# buses.net
KiCad netlist of a schematic drawn in EAGLE
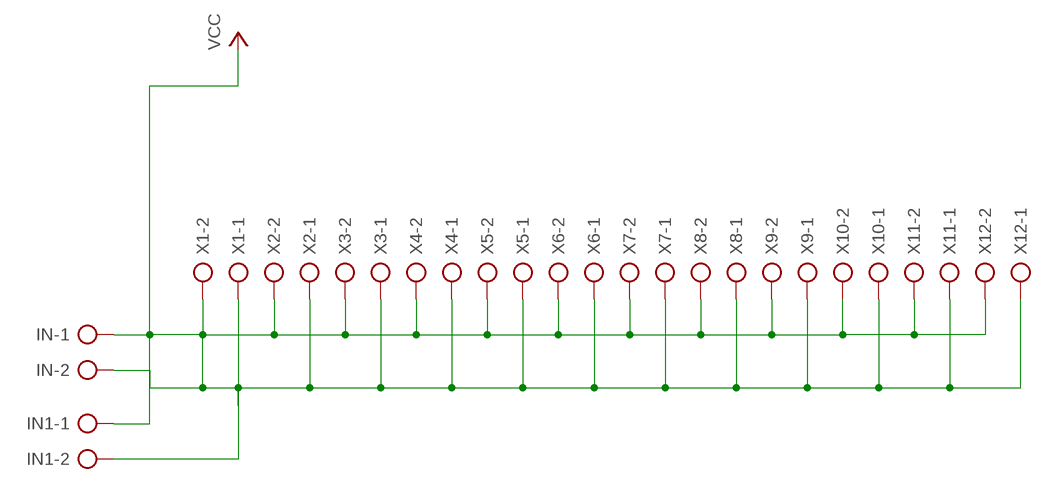
[diagram p0: schematic, sheet 1]

(export (version "E")
  (design (tool "Eeschema 10.0.6"))
  (components
    (comp (ref "IN")
      (value "AK500/2-H")
      (footprint "eagle-import:AK500_2-H")
      (libsource (lib "eagle-import") (part "AK500/2-H"))
    )
    (comp (ref "IN1")
      (value "AK500/2-H")
      (footprint "eagle-import:AK500_2-H")
      (libsource (lib "eagle-import") (part "AK500/2-H"))
    )
    (comp (ref "X1")
      (value "AK500/2-H")
      (footprint "eagle-import:AK500_2-H")
      (libsource (lib "eagle-import") (part "AK500/2-H"))
    )
    (comp (ref "X2")
      (value "AK500/2-H")
      (footprint "eagle-import:AK500_2-H")
      (libsource (lib "eagle-import") (part "AK500/2-H"))
    )
    (comp (ref "X3")
      (value "AK500/2-H")
      (footprint "eagle-import:AK500_2-H")
      (libsource (lib "eagle-import") (part "AK500/2-H"))
    )
    (comp (ref "X4")
      (value "AK500/2-H")
      (footprint "eagle-import:AK500_2-H")
      (libsource (lib "eagle-import") (part "AK500/2-H"))
    )
    (comp (ref "X5")
      (value "AK500/2-H")
      (footprint "eagle-import:AK500_2-H")
      (libsource (lib "eagle-import") (part "AK500/2-H"))
    )
    (comp (ref "X6")
      (value "AK500/2-H")
      (footprint "eagle-import:AK500_2-H")
      (libsource (lib "eagle-import") (part "AK500/2-H"))
    )
    (comp (ref "X7")
      (value "AK500/2-H")
      (footprint "eagle-import:AK500_2-H")
      (libsource (lib "eagle-import") (part "AK500/2-H"))
    )
    (comp (ref "X8")
      (value "AK500/2-H")
      (footprint "eagle-import:AK500_2-H")
      (libsource (lib "eagle-import") (part "AK500/2-H"))
    )
    (comp (ref "X9")
      (value "AK500/2-H")
      (footprint "eagle-import:AK500_2-H")
      (libsource (lib "eagle-import") (part "AK500/2-H"))
    )
    (comp (ref "X10")
      (value "AK500/2-H")
      (footprint "eagle-import:AK500_2-H")
      (libsource (lib "eagle-import") (part "AK500/2-H"))
    )
    (comp (ref "X11")
      (value "AK500/2-H")
      (footprint "eagle-import:AK500_2-H")
      (libsource (lib "eagle-import") (part "AK500/2-H"))
    )
    (comp (ref "X12")
      (value "AK500/2-H")
      (footprint "eagle-import:AK500_2-H")
      (libsource (lib "eagle-import") (part "AK500/2-H"))
    )
  )
  (nets
    (net (code "1") (name "VCC") (class "Default")
      (node (ref "IN") (pin "1") (pinfunction "KL_1") (pintype "passive"))
      (node (ref "IN") (pin "2") (pinfunction "KL_2") (pintype "passive"))
      (node (ref "IN1") (pin "1") (pinfunction "KL_1") (pintype "passive"))
      (node (ref "IN1") (pin "2") (pinfunction "KL_2") (pintype "passive"))
      (node (ref "X1") (pin "1") (pinfunction "KL_1") (pintype "passive"))
      (node (ref "X1") (pin "2") (pinfunction "KL_2") (pintype "passive"))
      (node (ref "X10") (pin "1") (pinfunction "KL_1") (pintype "passive"))
      (node (ref "X10") (pin "2") (pinfunction "KL_2") (pintype "passive"))
      (node (ref "X11") (pin "1") (pinfunction "KL_1") (pintype "passive"))
      (node (ref "X11") (pin "2") (pinfunction "KL_2") (pintype "passive"))
      (node (ref "X12") (pin "1") (pinfunction "KL_1") (pintype "passive"))
      (node (ref "X12") (pin "2") (pinfunction "KL_2") (pintype "passive"))
      (node (ref "X2") (pin "1") (pinfunction "KL_1") (pintype "passive"))
      (node (ref "X2") (pin "2") (pinfunction "KL_2") (pintype "passive"))
      (node (ref "X3") (pin "1") (pinfunction "KL_1") (pintype "passive"))
      (node (ref "X3") (pin "2") (pinfunction "KL_2") (pintype "passive"))
      (node (ref "X4") (pin "1") (pinfunction "KL_1") (pintype "passive"))
      (node (ref "X4") (pin "2") (pinfunction "KL_2") (pintype "passive"))
      (node (ref "X5") (pin "1") (pinfunction "KL_1") (pintype "passive"))
      (node (ref "X5") (pin "2") (pinfunction "KL_2") (pintype "passive"))
      (node (ref "X6") (pin "1") (pinfunction "KL_1") (pintype "passive"))
      (node (ref "X6") (pin "2") (pinfunction "KL_2") (pintype "passive"))
      (node (ref "X7") (pin "1") (pinfunction "KL_1") (pintype "passive"))
      (node (ref "X7") (pin "2") (pinfunction "KL_2") (pintype "passive"))
      (node (ref "X8") (pin "1") (pinfunction "KL_1") (pintype "passive"))
      (node (ref "X8") (pin "2") (pinfunction "KL_2") (pintype "passive"))
      (node (ref "X9") (pin "1") (pinfunction "KL_1") (pintype "passive"))
      (node (ref "X9") (pin "2") (pinfunction "KL_2") (pintype "passive"))
    )
  )
)
